# Indicators.net
KiCad netlist of a schematic drawn in Altium Designer
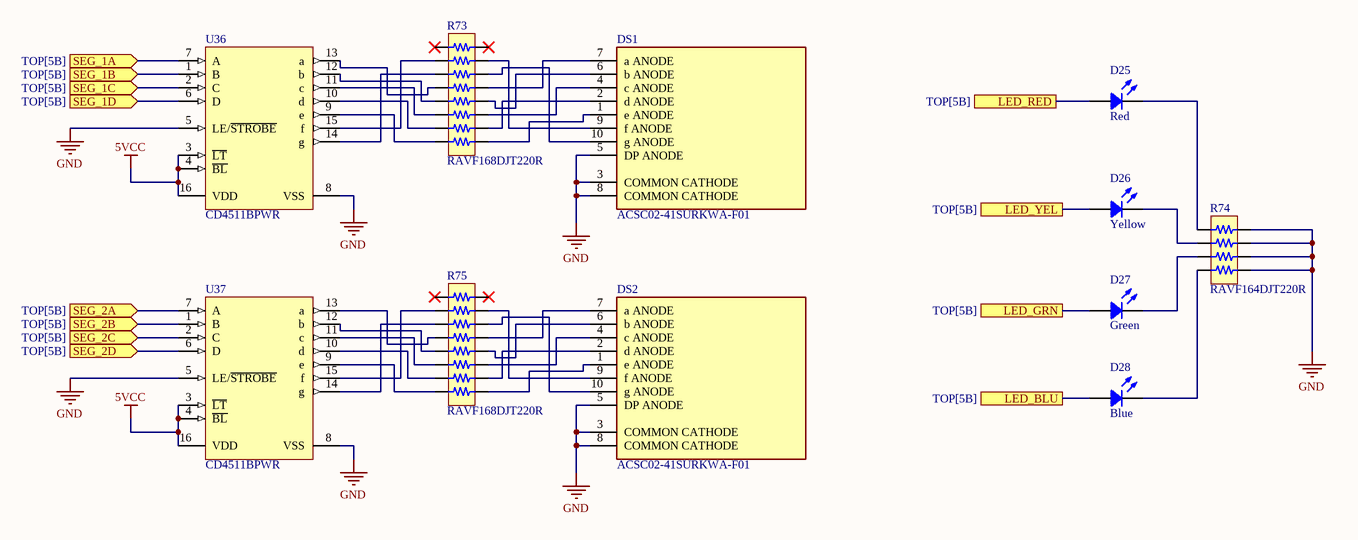
[diagram p0: Indicators.SchDoc]

(export (version "E")
  (design (tool "Eeschema 10.0.6"))
  (components
    (comp (ref "D25")
      (value "Red")
      (footprint "LED 0805_2012 RED")
      (description "LED RED CLEAR 0805 SMD")
      (fields (field (name "PART NUMBER") "SM0805URC") (field (name "MANUFACTURER") "Bivar Inc."))
      (libsource (lib "altium_library") (part "LED"))
    )
    (comp (ref "D26")
      (value "Yellow")
      (footprint "LED 0805_2012 YELLOW")
      (description "LED YELLOW CLEAR 0805 SMD")
      (fields (field (name "PART NUMBER") "SM0805UYC") (field (name "MANUFACTURER") "Bivar Inc."))
      (libsource (lib "altium_library") (part "LED"))
    )
    (comp (ref "D27")
      (value "Green")
      (footprint "LED 0805_2012 GREEN")
      (description "LED GREEN CLEAR 0805 SMD")
      (fields (field (name "PART NUMBER") "SM0805UGC") (field (name "MANUFACTURER") "Bivar Inc."))
      (libsource (lib "altium_library") (part "LED"))
    )
    (comp (ref "D28")
      (value "Blue")
      (footprint "LED 0805_2012 BLUE")
      (description "LED BLUE CLEAR 0805 SMD")
      (fields (field (name "PART NUMBER") "SM0805UBWC") (field (name "MANUFACTURER") "Bivar Inc."))
      (libsource (lib "altium_library") (part "LED"))
    )
    (comp (ref "DS1")
      (value "ACSC02-41SURKWA-F01")
      (footprint "FP-ACSC02-41SURKWA-F01-MFG")
      (description "DISPLAY 7-SEG 0.2\" SGL RED 10SMD")
      (libsource (lib "Altium Content Vault") (part "0e920bf6b93db43d611184977c40d65"))
    )
    (comp (ref "DS2")
      (value "ACSC02-41SURKWA-F01")
      (footprint "FP-ACSC02-41SURKWA-F01-MFG")
      (description "DISPLAY 7-SEG 0.2\" SGL RED 10SMD")
      (libsource (lib "Altium Content Vault") (part "0e920bf6b93db43d611184977c40d65"))
    )
    (comp (ref "R73")
      (value "RAVF168DJT220R")
      (footprint "RESNET 1506-16 CONVEX")
      (description "RES ARRAY 8 RES 220 OHM 1506")
      (fields (field (name "MANUFACTURER") "Stackpole Electronics Inc") (field (name "TOLERANCE") "±5%"))
      (libsource (lib "Celestial Altium Library - altium_library") (part "Resistor Array (8 Circuit)"))
    )
    (comp (ref "R74")
      (value "RAVF164DJT220R")
      (footprint "RESNET 1206-8 CONVEX")
      (description "RES ARRAY 4 RES 220 OHM 1206")
      (fields (field (name "MANUFACTURER") "Stackpole Electronics Inc") (field (name "TOLERANCE") "±5%"))
      (libsource (lib "Celestial Altium Library - altium_library") (part "Resistor Array (4 circuit)"))
    )
    (comp (ref "R75")
      (value "RAVF168DJT220R")
      (footprint "RESNET 1506-16 CONVEX")
      (description "RES ARRAY 8 RES 220 OHM 1506")
      (fields (field (name "MANUFACTURER") "Stackpole Electronics Inc") (field (name "TOLERANCE") "±5%"))
      (libsource (lib "Celestial Altium Library - altium_library") (part "Resistor Array (8 Circuit)"))
    )
    (comp (ref "U36")
      (value "CD4511BPWR")
      (footprint "PW0016A_N")
      (fields (field (name "MANUFACTURER") "Texas Instruments"))
      (libsource (lib "Altium Content Vault") (part "TI-CD4511B-16"))
    )
    (comp (ref "U37")
      (value "CD4511BPWR")
      (footprint "PW0016A_N")
      (fields (field (name "MANUFACTURER") "Texas Instruments"))
      (libsource (lib "Altium Content Vault") (part "TI-CD4511B-16"))
    )
  )
  (nets
    (net (code "1") (name "/LED_BLU") (class "Default")
      (node (ref "D28") (pin "1") (pinfunction "1_1") (pintype "passive"))
    )
    (net (code "2") (name "/LED_GRN") (class "Default")
      (node (ref "D27") (pin "1") (pinfunction "1_1") (pintype "passive"))
    )
    (net (code "3") (name "/LED_RED") (class "Default")
      (node (ref "D25") (pin "1") (pinfunction "1_1") (pintype "passive"))
    )
    (net (code "4") (name "/LED_YEL") (class "Default")
      (node (ref "D26") (pin "1") (pinfunction "1_1") (pintype "passive"))
    )
    (net (code "5") (name "/SEG_1A") (class "Default")
      (node (ref "U36") (pin "7") (pinfunction "A_7") (pintype "input"))
    )
    (net (code "6") (name "/SEG_1B") (class "Default")
      (node (ref "U36") (pin "1") (pinfunction "B_1") (pintype "input"))
    )
    (net (code "7") (name "/SEG_1C") (class "Default")
      (node (ref "U36") (pin "2") (pinfunction "C_2") (pintype "input"))
    )
    (net (code "8") (name "/SEG_1D") (class "Default")
      (node (ref "U36") (pin "6") (pinfunction "D_6") (pintype "input"))
    )
    (net (code "9") (name "/SEG_2A") (class "Default")
      (node (ref "U37") (pin "7") (pinfunction "A_7") (pintype "input"))
    )
    (net (code "10") (name "/SEG_2B") (class "Default")
      (node (ref "U37") (pin "1") (pinfunction "B_1") (pintype "input"))
    )
    (net (code "11") (name "/SEG_2C") (class "Default")
      (node (ref "U37") (pin "2") (pinfunction "C_2") (pintype "input"))
    )
    (net (code "12") (name "/SEG_2D") (class "Default")
      (node (ref "U37") (pin "6") (pinfunction "D_6") (pintype "input"))
    )
    (net (code "13") (name "5VCC") (class "Default")
      (node (ref "U36") (pin "16") (pinfunction "VDD_16") (pintype "power_in"))
      (node (ref "U36") (pin "3") (pinfunction "~{LT}_3") (pintype "input"))
      (node (ref "U36") (pin "4") (pinfunction "~{BL}_4") (pintype "input"))
      (node (ref "U37") (pin "16") (pinfunction "VDD_16") (pintype "power_in"))
      (node (ref "U37") (pin "3") (pinfunction "~{LT}_3") (pintype "input"))
      (node (ref "U37") (pin "4") (pinfunction "~{BL}_4") (pintype "input"))
    )
    (net (code "14") (name "GND") (class "Default")
      (node (ref "DS1") (pin "3") (pinfunction "COMMON_CATHODE_3") (pintype "passive"))
      (node (ref "DS1") (pin "5") (pinfunction "DP_ANODE_5") (pintype "passive"))
      (node (ref "DS1") (pin "8") (pinfunction "COMMON_CATHODE_8") (pintype "passive"))
      (node (ref "DS2") (pin "3") (pinfunction "COMMON_CATHODE_3") (pintype "passive"))
      (node (ref "DS2") (pin "5") (pinfunction "DP_ANODE_5") (pintype "passive"))
      (node (ref "DS2") (pin "8") (pinfunction "COMMON_CATHODE_8") (pintype "passive"))
      (node (ref "R74") (pin "5") (pinfunction "5_5") (pintype "passive"))
      (node (ref "R74") (pin "6") (pinfunction "6_6") (pintype "passive"))
      (node (ref "R74") (pin "7") (pinfunction "7_7") (pintype "passive"))
      (node (ref "R74") (pin "8") (pinfunction "8_8") (pintype "passive"))
      (node (ref "U36") (pin "5") (pinfunction "LE/~{STROBE}_5") (pintype "input"))
      (node (ref "U36") (pin "8") (pinfunction "VSS_8") (pintype "power_in"))
      (node (ref "U37") (pin "5") (pinfunction "LE/~{STROBE}_5") (pintype "input"))
      (node (ref "U37") (pin "8") (pinfunction "VSS_8") (pintype "power_in"))
    )
    (net (code "15") (name "Net-(D25-Pad2)") (class "Default")
      (node (ref "D25") (pin "2") (pinfunction "2_2") (pintype "passive"))
      (node (ref "R74") (pin "1") (pinfunction "1_1") (pintype "passive"))
    )
    (net (code "16") (name "Net-(D26-Pad2)") (class "Default")
      (node (ref "D26") (pin "2") (pinfunction "2_2") (pintype "passive"))
      (node (ref "R74") (pin "2") (pinfunction "2_2") (pintype "passive"))
    )
    (net (code "17") (name "Net-(D27-Pad2)") (class "Default")
      (node (ref "D27") (pin "2") (pinfunction "2_2") (pintype "passive"))
      (node (ref "R74") (pin "3") (pinfunction "3_3") (pintype "passive"))
    )
    (net (code "18") (name "Net-(D28-Pad2)") (class "Default")
      (node (ref "D28") (pin "2") (pinfunction "2_2") (pintype "passive"))
      (node (ref "R74") (pin "4") (pinfunction "4_4") (pintype "passive"))
    )
    (net (code "19") (name "Net-(DS1-a_ANODE)") (class "Default")
      (node (ref "DS1") (pin "7") (pinfunction "a_ANODE_7") (pintype "passive"))
      (node (ref "R73") (pin "13") (pinfunction "13_13") (pintype "passive"))
    )
    (net (code "20") (name "Net-(DS1-b_ANODE)") (class "Default")
      (node (ref "DS1") (pin "6") (pinfunction "b_ANODE_6") (pintype "passive"))
      (node (ref "R73") (pin "12") (pinfunction "12_12") (pintype "passive"))
    )
    (net (code "21") (name "Net-(DS1-c_ANODE)") (class "Default")
      (node (ref "DS1") (pin "4") (pinfunction "c_ANODE_4") (pintype "passive"))
      (node (ref "R73") (pin "11") (pinfunction "11_11") (pintype "passive"))
    )
    (net (code "22") (name "Net-(DS1-d_ANODE)") (class "Default")
      (node (ref "DS1") (pin "2") (pinfunction "d_ANODE_2") (pintype "passive"))
      (node (ref "R73") (pin "10") (pinfunction "10_10") (pintype "passive"))
    )
    (net (code "23") (name "Net-(DS1-e_ANODE)") (class "Default")
      (node (ref "DS1") (pin "1") (pinfunction "e_ANODE_1") (pintype "passive"))
      (node (ref "R73") (pin "9") (pinfunction "9_9") (pintype "passive"))
    )
    (net (code "24") (name "Net-(DS1-f_ANODE)") (class "Default")
      (node (ref "DS1") (pin "9") (pinfunction "f_ANODE_9") (pintype "passive"))
      (node (ref "R73") (pin "15") (pinfunction "15_15") (pintype "passive"))
    )
    (net (code "25") (name "Net-(DS1-g_ANODE)") (class "Default")
      (node (ref "DS1") (pin "10") (pinfunction "g_ANODE_10") (pintype "passive"))
      (node (ref "R73") (pin "14") (pinfunction "14_14") (pintype "passive"))
    )
    (net (code "26") (name "Net-(DS2-a_ANODE)") (class "Default")
      (node (ref "DS2") (pin "7") (pinfunction "a_ANODE_7") (pintype "passive"))
      (node (ref "R75") (pin "13") (pinfunction "13_13") (pintype "passive"))
    )
    (net (code "27") (name "Net-(DS2-b_ANODE)") (class "Default")
      (node (ref "DS2") (pin "6") (pinfunction "b_ANODE_6") (pintype "passive"))
      (node (ref "R75") (pin "12") (pinfunction "12_12") (pintype "passive"))
    )
    (net (code "28") (name "Net-(DS2-c_ANODE)") (class "Default")
      (node (ref "DS2") (pin "4") (pinfunction "c_ANODE_4") (pintype "passive"))
      (node (ref "R75") (pin "11") (pinfunction "11_11") (pintype "passive"))
    )
    (net (code "29") (name "Net-(DS2-d_ANODE)") (class "Default")
      (node (ref "DS2") (pin "2") (pinfunction "d_ANODE_2") (pintype "passive"))
      (node (ref "R75") (pin "10") (pinfunction "10_10") (pintype "passive"))
    )
    (net (code "30") (name "Net-(DS2-e_ANODE)") (class "Default")
      (node (ref "DS2") (pin "1") (pinfunction "e_ANODE_1") (pintype "passive"))
      (node (ref "R75") (pin "9") (pinfunction "9_9") (pintype "passive"))
    )
    (net (code "31") (name "Net-(DS2-f_ANODE)") (class "Default")
      (node (ref "DS2") (pin "9") (pinfunction "f_ANODE_9") (pintype "passive"))
      (node (ref "R75") (pin "15") (pinfunction "15_15") (pintype "passive"))
    )
    (net (code "32") (name "Net-(DS2-g_ANODE)") (class "Default")
      (node (ref "DS2") (pin "10") (pinfunction "g_ANODE_10") (pintype "passive"))
      (node (ref "R75") (pin "14") (pinfunction "14_14") (pintype "passive"))
    )
    (net (code "33") (name "Net-(U36-a)") (class "Default")
      (node (ref "R73") (pin "4") (pinfunction "4_4") (pintype "passive"))
      (node (ref "U36") (pin "13") (pinfunction "a_13") (pintype "output"))
    )
    (net (code "34") (name "Net-(U36-b)") (class "Default")
      (node (ref "R73") (pin "5") (pinfunction "6_5") (pintype "passive"))
      (node (ref "U36") (pin "12") (pinfunction "b_12") (pintype "output"))
    )
    (net (code "35") (name "Net-(U36-c)") (class "Default")
      (node (ref "R73") (pin "6") (pinfunction "6_6") (pintype "passive"))
      (node (ref "U36") (pin "11") (pinfunction "c_11") (pintype "output"))
    )
    (net (code "36") (name "Net-(U36-d)") (class "Default")
      (node (ref "R73") (pin "7") (pinfunction "7_7") (pintype "passive"))
      (node (ref "U36") (pin "10") (pinfunction "d_10") (pintype "output"))
    )
    (net (code "37") (name "Net-(U36-e)") (class "Default")
      (node (ref "R73") (pin "8") (pinfunction "8_8") (pintype "passive"))
      (node (ref "U36") (pin "9") (pinfunction "e_9") (pintype "output"))
    )
    (net (code "38") (name "Net-(U36-f)") (class "Default")
      (node (ref "R73") (pin "2") (pinfunction "2_2") (pintype "passive"))
      (node (ref "U36") (pin "15") (pinfunction "f_15") (pintype "output"))
    )
    (net (code "39") (name "Net-(U36-g)") (class "Default")
      (node (ref "R73") (pin "3") (pinfunction "3_3") (pintype "passive"))
      (node (ref "U36") (pin "14") (pinfunction "g_14") (pintype "output"))
    )
    (net (code "40") (name "Net-(U37-a)") (class "Default")
      (node (ref "R75") (pin "4") (pinfunction "4_4") (pintype "passive"))
      (node (ref "U37") (pin "13") (pinfunction "a_13") (pintype "output"))
    )
    (net (code "41") (name "Net-(U37-b)") (class "Default")
      (node (ref "R75") (pin "5") (pinfunction "6_5") (pintype "passive"))
      (node (ref "U37") (pin "12") (pinfunction "b_12") (pintype "output"))
    )
    (net (code "42") (name "Net-(U37-c)") (class "Default")
      (node (ref "R75") (pin "6") (pinfunction "6_6") (pintype "passive"))
      (node (ref "U37") (pin "11") (pinfunction "c_11") (pintype "output"))
    )
    (net (code "43") (name "Net-(U37-d)") (class "Default")
      (node (ref "R75") (pin "7") (pinfunction "7_7") (pintype "passive"))
      (node (ref "U37") (pin "10") (pinfunction "d_10") (pintype "output"))
    )
    (net (code "44") (name "Net-(U37-e)") (class "Default")
      (node (ref "R75") (pin "8") (pinfunction "8_8") (pintype "passive"))
      (node (ref "U37") (pin "9") (pinfunction "e_9") (pintype "output"))
    )
    (net (code "45") (name "Net-(U37-f)") (class "Default")
      (node (ref "R75") (pin "2") (pinfunction "2_2") (pintype "passive"))
      (node (ref "U37") (pin "15") (pinfunction "f_15") (pintype "output"))
    )
    (net (code "46") (name "Net-(U37-g)") (class "Default")
      (node (ref "R75") (pin "3") (pinfunction "3_3") (pintype "passive"))
      (node (ref "U37") (pin "14") (pinfunction "g_14") (pintype "output"))
    )
    (net (code "47") (name "unconnected-(R73-Pad1)") (class "Default")
      (node (ref "R73") (pin "1") (pinfunction "1_1") (pintype "passive+no_connect"))
    )
    (net (code "48") (name "unconnected-(R73-Pad16)") (class "Default")
      (node (ref "R73") (pin "16") (pinfunction "16_16") (pintype "passive+no_connect"))
    )
    (net (code "49") (name "unconnected-(R75-Pad1)") (class "Default")
      (node (ref "R75") (pin "1") (pinfunction "1_1") (pintype "passive+no_connect"))
    )
    (net (code "50") (name "unconnected-(R75-Pad16)") (class "Default")
      (node (ref "R75") (pin "16") (pinfunction "16_16") (pintype "passive+no_connect"))
    )
  )
)
